# SHC_machnguon_v2.net
KiCad netlist of a schematic drawn in Altium Designer
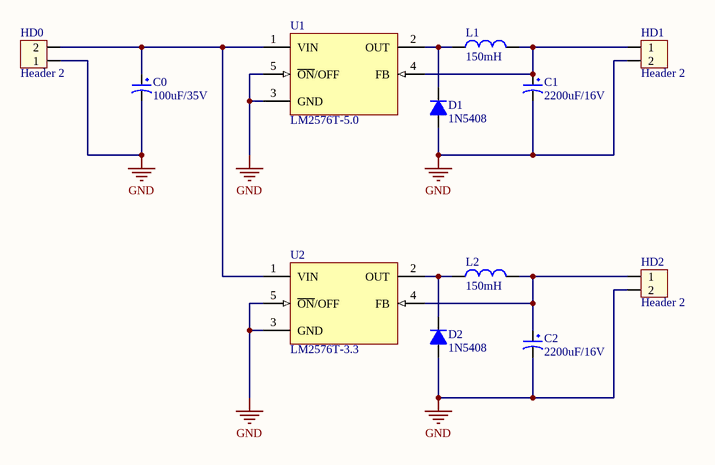
[diagram p0: SHC_machnguon_v2.SchDoc]

(export (version "E")
  (design (tool "Eeschema 10.0.6"))
  (components
    (comp (ref "C0")
      (value "100uF/35V")
      (footprint "CP1.5/3.4")
      (description "Cap 100uF/35V - 470uF/16V")
      (libsource (lib "syhaunguyen") (part "CP3"))
    )
    (comp (ref "C1")
      (value "2200uF/16V")
      (footprint "CP2/4")
      (description "Cap 2200uF/16V - 1000uF/50V")
      (libsource (lib "VioletofSun") (part "CP5"))
    )
    (comp (ref "C2")
      (value "2200uF/16V")
      (footprint "CP2/4")
      (description "Cap 2200uF/16V - 1000uF/50V")
      (libsource (lib "VioletofSun") (part "CP5"))
    )
    (comp (ref "D1")
      (value "1N5408")
      (footprint "D5A")
      (description "Diode 5A")
      (libsource (lib "syhaunguyen") (part "D5A"))
    )
    (comp (ref "D2")
      (value "1N5408")
      (footprint "D5A")
      (description "Diode 5A")
      (libsource (lib "syhaunguyen") (part "D5A"))
    )
    (comp (ref "HD0")
      (value "Header 2")
      (footprint "HED2")
      (description "Header 2 (Green)")
      (libsource (lib "VioletofSun") (part "Hed2"))
    )
    (comp (ref "HD1")
      (value "Header 2")
      (footprint "HED2")
      (description "Header 2 (Green)")
      (libsource (lib "") (part "Hed2_1"))
    )
    (comp (ref "HD2")
      (value "Header 2")
      (footprint "HED2")
      (description "Header 2 (Green)")
      (libsource (lib "") (part "Hed2_1"))
    )
    (comp (ref "L1")
      (value "150mH")
      (footprint "L/0.4")
      (description "Inductor")
      (libsource (lib "VioletofSun") (part "L1"))
    )
    (comp (ref "L2")
      (value "150mH")
      (footprint "L/0.4")
      (description "Inductor")
      (libsource (lib "VioletofSun") (part "L1"))
    )
    (comp (ref "U1")
      (value "LM2576T-5.0")
      (footprint "LM2576t")
      (description "SIMPLE SWITCHER; 3A Step-Down Voltage Regulator")
      (fields
        (field (name "MANUFACTURER") "National Semiconductor")
        (field (name "DIGIKEYPARTNUMBER") "LM2576T-5.0-ND")
        (field (name "PUBLISHER") "Altium Limited")
      )
      (libsource (lib "General IC") (part "LM2576T-5.0"))
    )
    (comp (ref "U2")
      (value "LM2576T-3.3")
      (footprint "LM2576t")
      (description "SIMPLE SWITCHER; 3A Step-Down Voltage Regulator")
      (fields
        (field (name "PARTNUMBER") "LM2576T-5.0")
        (field (name "MANUFACTURER") "National Semiconductor")
        (field (name "PUBLISHER") "Altium Limited")
      )
      (libsource (lib "General IC") (part "LM2576T-5.0"))
    )
  )
  (nets
    (net (code "1") (name "GND") (class "Default")
      (node (ref "C0") (pin "2") (pinfunction "2_2") (pintype "passive"))
      (node (ref "C1") (pin "2") (pinfunction "2_2") (pintype "passive"))
      (node (ref "C2") (pin "2") (pinfunction "2_2") (pintype "passive"))
      (node (ref "D1") (pin "1") (pinfunction "A_1") (pintype "passive"))
      (node (ref "D2") (pin "1") (pinfunction "A_1") (pintype "passive"))
      (node (ref "HD0") (pin "1") (pinfunction "1_1") (pintype "passive"))
      (node (ref "HD1") (pin "2") (pinfunction "2_2") (pintype "passive"))
      (node (ref "HD2") (pin "2") (pinfunction "2_2") (pintype "passive"))
      (node (ref "U1") (pin "3") (pinfunction "GND_3") (pintype "power_in"))
      (node (ref "U1") (pin "5") (pinfunction "~{ON}/OFF_5") (pintype "input"))
      (node (ref "U2") (pin "3") (pinfunction "GND_3") (pintype "power_in"))
      (node (ref "U2") (pin "5") (pinfunction "~{ON}/OFF_5") (pintype "input"))
    )
    (net (code "2") (name "Net-(D1-K)") (class "Default")
      (node (ref "D1") (pin "2") (pinfunction "K_2") (pintype "passive"))
      (node (ref "L1") (pin "1") (pinfunction "1_1") (pintype "passive"))
      (node (ref "U1") (pin "2") (pinfunction "OUT_2") (pintype "power_in"))
    )
    (net (code "3") (name "Net-(D2-K)") (class "Default")
      (node (ref "D2") (pin "2") (pinfunction "K_2") (pintype "passive"))
      (node (ref "L2") (pin "1") (pinfunction "1_1") (pintype "passive"))
      (node (ref "U2") (pin "2") (pinfunction "OUT_2") (pintype "power_in"))
    )
    (net (code "4") (name "Net-(U1-FB)") (class "Default")
      (node (ref "C1") (pin "1") (pinfunction "1_1") (pintype "passive"))
      (node (ref "HD1") (pin "1") (pinfunction "1_1") (pintype "passive"))
      (node (ref "L1") (pin "2") (pinfunction "2_2") (pintype "passive"))
      (node (ref "U1") (pin "4") (pinfunction "FB_4") (pintype "input"))
    )
    (net (code "5") (name "Net-(U1-VIN)") (class "Default")
      (node (ref "C0") (pin "1") (pinfunction "1_1") (pintype "passive"))
      (node (ref "HD0") (pin "2") (pinfunction "2_2") (pintype "passive"))
      (node (ref "U1") (pin "1") (pinfunction "VIN_1") (pintype "power_in"))
      (node (ref "U2") (pin "1") (pinfunction "VIN_1") (pintype "power_in"))
    )
    (net (code "6") (name "Net-(U2-FB)") (class "Default")
      (node (ref "C2") (pin "1") (pinfunction "1_1") (pintype "passive"))
      (node (ref "HD2") (pin "1") (pinfunction "1_1") (pintype "passive"))
      (node (ref "L2") (pin "2") (pinfunction "2_2") (pintype "passive"))
      (node (ref "U2") (pin "4") (pinfunction "FB_4") (pintype "input"))
    )
  )
)
